# v1_3SMD.net
KiCad netlist of a schematic drawn in EAGLE
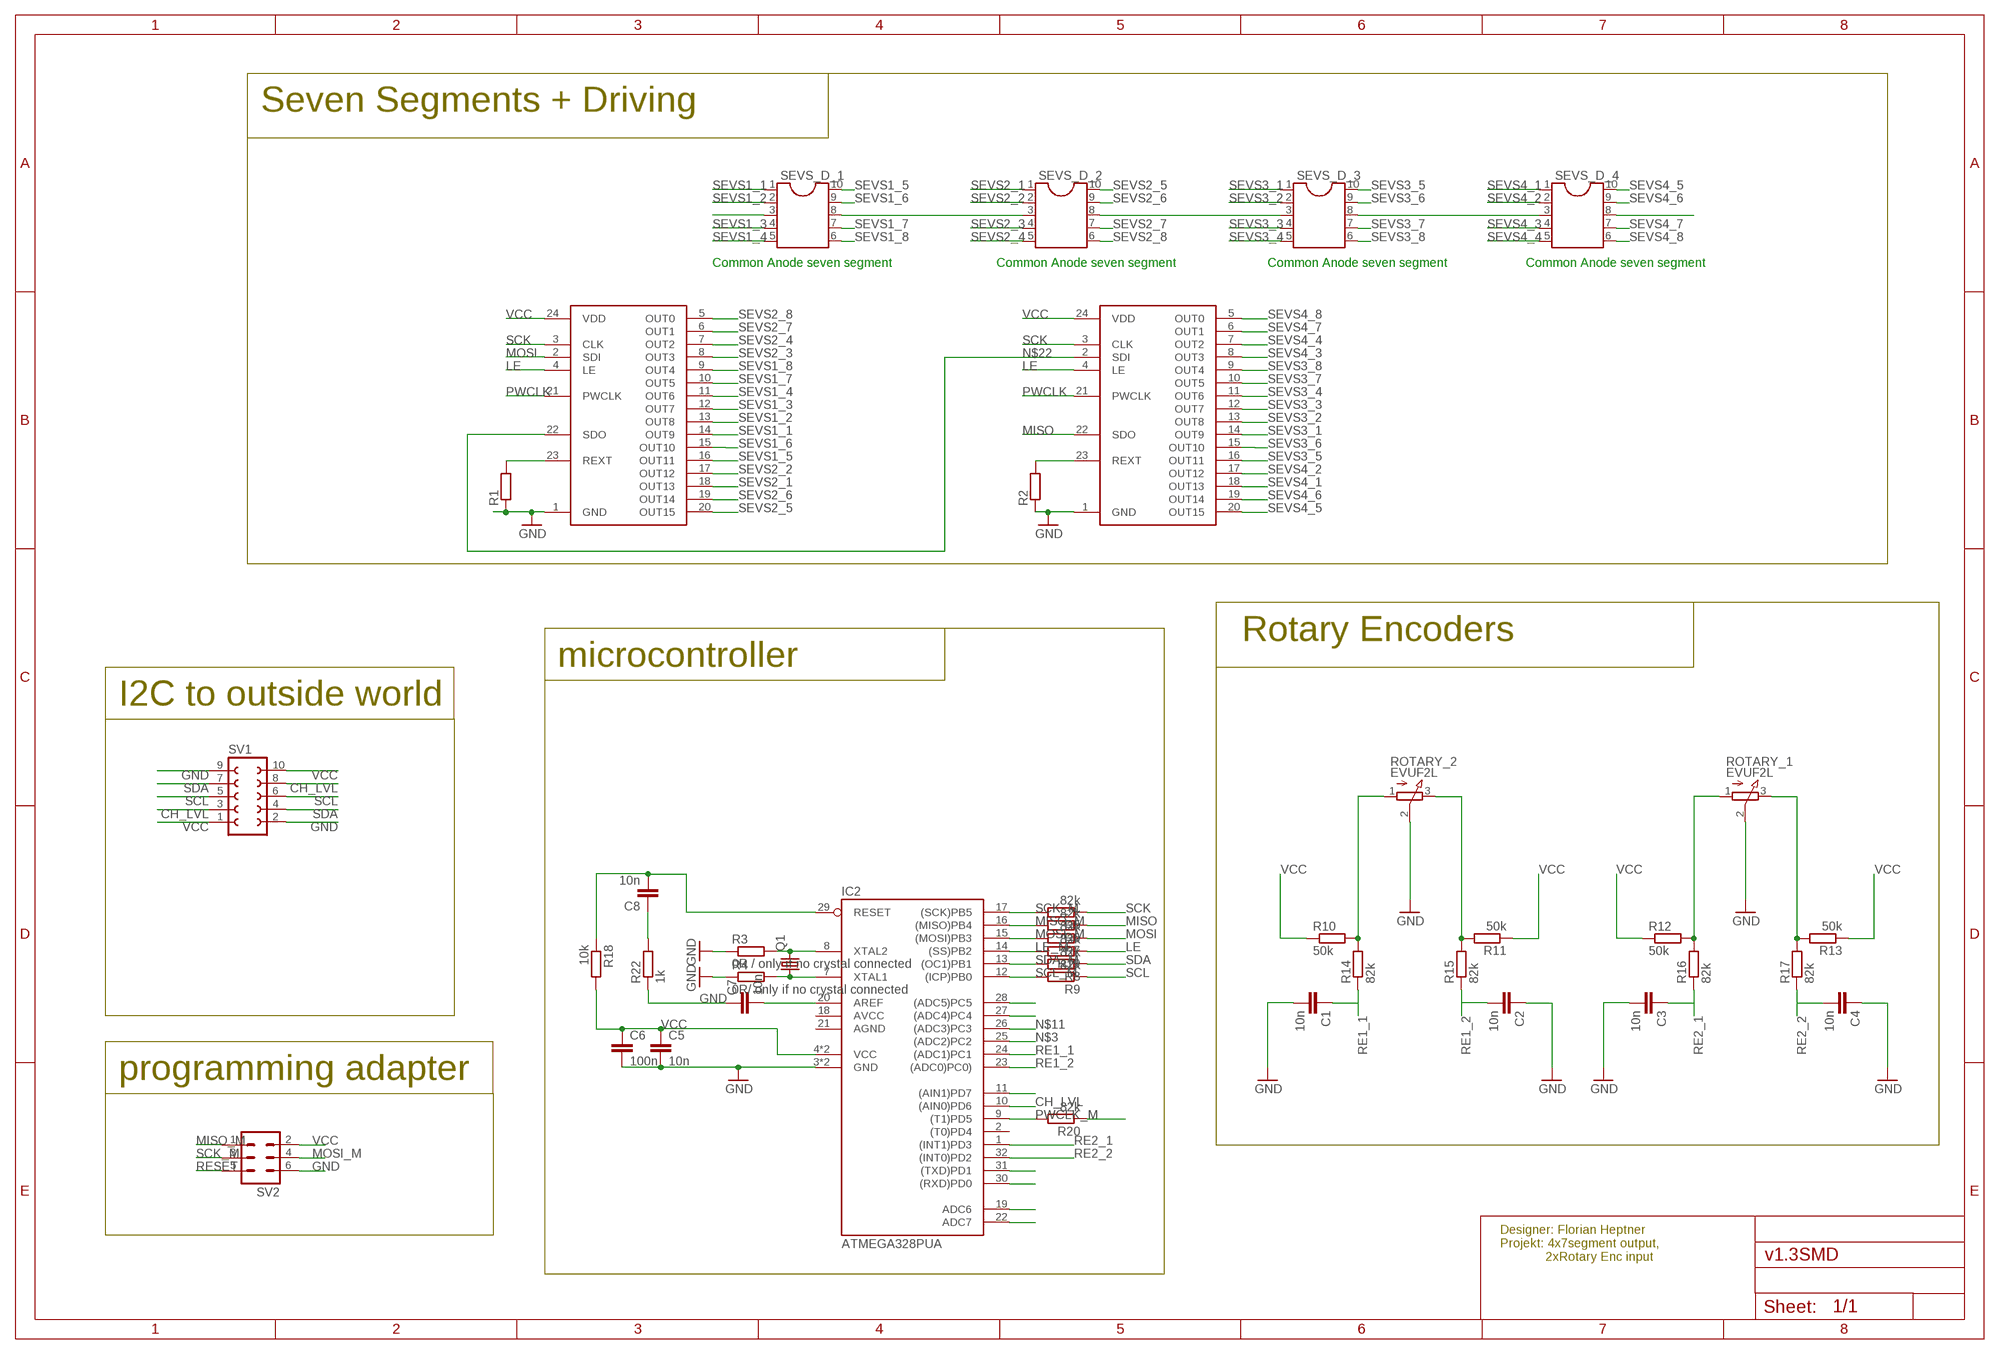
[diagram p0: schematic, sheet 1]

(export (version "E")
  (design (tool "Eeschema 10.0.6"))
  (components
    (comp (ref "C1")
      (value "10n")
      (footprint "eagle-import:C0603")
      (libsource (lib "eagle-import") (part "C-EUC0603"))
    )
    (comp (ref "C2")
      (value "10n")
      (footprint "eagle-import:C0603")
      (libsource (lib "eagle-import") (part "C-EUC0603"))
    )
    (comp (ref "C3")
      (value "10n")
      (footprint "eagle-import:C0603")
      (libsource (lib "eagle-import") (part "C-EUC0603"))
    )
    (comp (ref "C4")
      (value "10n")
      (footprint "eagle-import:C0603")
      (libsource (lib "eagle-import") (part "C-EUC0603"))
    )
    (comp (ref "C5")
      (value "10n")
      (footprint "eagle-import:C0603")
      (libsource (lib "eagle-import") (part "C-EUC0603"))
    )
    (comp (ref "C6")
      (value "100n")
      (footprint "eagle-import:C0603")
      (libsource (lib "eagle-import") (part "C-EUC0603"))
    )
    (comp (ref "C7")
      (value "10n")
      (footprint "eagle-import:C0603")
      (libsource (lib "eagle-import") (part "C-EUC0603"))
    )
    (comp (ref "C8")
      (value "10n")
      (footprint "eagle-import:C0603")
      (libsource (lib "eagle-import") (part "C-EUC0603"))
    )
    (comp (ref "IC2")
      (value "ATMEGA328PUA")
      (footprint "eagle-import:TQFP32-08")
      (libsource (lib "eagle-import") (part "ATMEGA328PUA"))
    )
    (comp (ref "Q1")
      (value "CRYSTALSM49")
      (footprint "eagle-import:SM49")
      (libsource (lib "eagle-import") (part "CRYSTALSM49"))
    )
    (comp (ref "R1")
      (value "R-EU_R0603")
      (footprint "eagle-import:R0603")
      (libsource (lib "eagle-import") (part "R-EU_R0603"))
    )
    (comp (ref "R2")
      (value "R-EU_R0603")
      (footprint "eagle-import:R0603")
      (libsource (lib "eagle-import") (part "R-EU_R0603"))
    )
    (comp (ref "R3")
      (value "0R / only if no crystal connected")
      (footprint "eagle-import:R0603")
      (libsource (lib "eagle-import") (part "R-EU_R0603"))
    )
    (comp (ref "R4")
      (value "0R/ only if no crystal connected")
      (footprint "eagle-import:R0603")
      (libsource (lib "eagle-import") (part "R-EU_R0603"))
    )
    (comp (ref "R5")
      (value "82k")
      (footprint "eagle-import:R0603")
      (libsource (lib "eagle-import") (part "R-EU_R0603"))
    )
    (comp (ref "R6")
      (value "82k")
      (footprint "eagle-import:R0603")
      (libsource (lib "eagle-import") (part "R-EU_R0603"))
    )
    (comp (ref "R7")
      (value "82k")
      (footprint "eagle-import:R0603")
      (libsource (lib "eagle-import") (part "R-EU_R0603"))
    )
    (comp (ref "R8")
      (value "82k")
      (footprint "eagle-import:R0603")
      (libsource (lib "eagle-import") (part "R-EU_R0603"))
    )
    (comp (ref "R9")
      (value "82k")
      (footprint "eagle-import:R0603")
      (libsource (lib "eagle-import") (part "R-EU_R0603"))
    )
    (comp (ref "R10")
      (value "50k")
      (footprint "eagle-import:R0603")
      (libsource (lib "eagle-import") (part "R-EU_R0603"))
    )
    (comp (ref "R11")
      (value "50k")
      (footprint "eagle-import:R0603")
      (libsource (lib "eagle-import") (part "R-EU_R0603"))
    )
    (comp (ref "R12")
      (value "50k")
      (footprint "eagle-import:R0603")
      (libsource (lib "eagle-import") (part "R-EU_R0603"))
    )
    (comp (ref "R13")
      (value "50k")
      (footprint "eagle-import:R0603")
      (libsource (lib "eagle-import") (part "R-EU_R0603"))
    )
    (comp (ref "R14")
      (value "82k")
      (footprint "eagle-import:R0603")
      (libsource (lib "eagle-import") (part "R-EU_R0603"))
    )
    (comp (ref "R15")
      (value "82k")
      (footprint "eagle-import:R0603")
      (libsource (lib "eagle-import") (part "R-EU_R0603"))
    )
    (comp (ref "R16")
      (value "82k")
      (footprint "eagle-import:R0603")
      (libsource (lib "eagle-import") (part "R-EU_R0603"))
    )
    (comp (ref "R17")
      (value "82k")
      (footprint "eagle-import:R0603")
      (libsource (lib "eagle-import") (part "R-EU_R0603"))
    )
    (comp (ref "R18")
      (value "10k")
      (footprint "eagle-import:R0603")
      (libsource (lib "eagle-import") (part "R-EU_R0603"))
    )
    (comp (ref "R19")
      (value "82k")
      (footprint "eagle-import:R0603")
      (libsource (lib "eagle-import") (part "R-EU_R0603"))
    )
    (comp (ref "R20")
      (value "82k")
      (footprint "eagle-import:R0603")
      (libsource (lib "eagle-import") (part "R-EU_R0603"))
    )
    (comp (ref "R22")
      (value "1k")
      (footprint "eagle-import:R0603")
      (libsource (lib "eagle-import") (part "R-EU_R0603"))
    )
    (comp (ref "ROTARY_1")
      (value "EVUF2L")
      (footprint "eagle-import:EVUFXL")
      (libsource (lib "eagle-import") (part "EVULF2"))
    )
    (comp (ref "ROTARY_2")
      (value "EVUF2L")
      (footprint "eagle-import:EVUFXL")
      (libsource (lib "eagle-import") (part "EVULF2"))
    )
    (comp (ref "SEVS_D_1")
      (value "DIL10")
      (footprint "eagle-import:DIL10")
      (libsource (lib "eagle-import") (part "DIL10"))
    )
    (comp (ref "SEVS_D_2")
      (value "DIL10")
      (footprint "eagle-import:DIL10")
      (libsource (lib "eagle-import") (part "DIL10"))
    )
    (comp (ref "SEVS_D_3")
      (value "DIL10")
      (footprint "eagle-import:DIL10")
      (libsource (lib "eagle-import") (part "DIL10"))
    )
    (comp (ref "SEVS_D_4")
      (value "DIL10")
      (footprint "eagle-import:DIL10")
      (libsource (lib "eagle-import") (part "DIL10"))
    )
    (comp (ref "SV1")
      (value "FE05-2")
      (footprint "eagle-import:FE05-2")
      (libsource (lib "eagle-import") (part "FE05-2"))
    )
    (comp (ref "SV2")
      (value "ML6")
      (footprint "eagle-import:ML6")
      (libsource (lib "eagle-import") (part "ML6"))
    )
    (comp (ref "U$1")
      (value "SPILEDDRIVER")
      (footprint "eagle-import:TSSOP24")
      (libsource (lib "eagle-import") (part "SPILEDDRIVER"))
    )
    (comp (ref "U$2")
      (value "SPILEDDRIVER")
      (footprint "eagle-import:TSSOP24")
      (libsource (lib "eagle-import") (part "SPILEDDRIVER"))
    )
  )
  (nets
    (net (code "1") (name "/AGND") (class "Default")
      (node (ref "IC2") (pin "21") (pinfunction "AGND_21") (pintype "power_in"))
    )
    (net (code "2") (name "/AVCC") (class "Default")
      (node (ref "IC2") (pin "18") (pinfunction "AVCC_18") (pintype "power_in"))
    )
    (net (code "3") (name "/CH_LVL") (class "Default")
      (node (ref "IC2") (pin "10") (pinfunction "(AIN0)PD6_10") (pintype "bidirectional"))
      (node (ref "SV1") (pin "3") (pinfunction "3_3") (pintype "passive"))
      (node (ref "SV1") (pin "8") (pinfunction "8_8") (pintype "passive"))
    )
    (net (code "4") (name "/LE") (class "Default")
      (node (ref "R19") (pin "1") (pinfunction "1_1") (pintype "passive"))
      (node (ref "U$1") (pin "4") (pinfunction "LE_4") (pintype "bidirectional"))
      (node (ref "U$2") (pin "4") (pinfunction "LE_4") (pintype "bidirectional"))
    )
    (net (code "5") (name "/LE_M") (class "Default")
      (node (ref "IC2") (pin "14") (pinfunction "(SS)PB2_14") (pintype "bidirectional"))
      (node (ref "R19") (pin "2") (pinfunction "2_2") (pintype "passive"))
    )
    (net (code "6") (name "/MISO") (class "Default")
      (node (ref "R6") (pin "1") (pinfunction "1_1") (pintype "passive"))
      (node (ref "U$2") (pin "22") (pinfunction "SDO_22") (pintype "bidirectional"))
    )
    (net (code "7") (name "/MISO_M") (class "Default")
      (node (ref "IC2") (pin "16") (pinfunction "(MISO)PB4_16") (pintype "bidirectional"))
      (node (ref "R6") (pin "2") (pinfunction "2_2") (pintype "passive"))
      (node (ref "SV2") (pin "1") (pinfunction "1_1") (pintype "passive"))
    )
    (net (code "8") (name "/MOSI") (class "Default")
      (node (ref "R7") (pin "1") (pinfunction "1_1") (pintype "passive"))
      (node (ref "U$1") (pin "2") (pinfunction "SDI_2") (pintype "bidirectional"))
    )
    (net (code "9") (name "/MOSI_M") (class "Default")
      (node (ref "IC2") (pin "15") (pinfunction "(MOSI)PB3_15") (pintype "bidirectional"))
      (node (ref "R7") (pin "2") (pinfunction "2_2") (pintype "passive"))
      (node (ref "SV2") (pin "4") (pinfunction "4_4") (pintype "passive"))
    )
    (net (code "10") (name "/N$3") (class "Default")
      (node (ref "IC2") (pin "25") (pinfunction "(ADC2)PC2_25") (pintype "bidirectional"))
    )
    (net (code "11") (name "/N$11") (class "Default")
      (node (ref "IC2") (pin "26") (pinfunction "(ADC3)PC3_26") (pintype "bidirectional"))
    )
    (net (code "12") (name "/N$22") (class "Default")
      (node (ref "U$1") (pin "22") (pinfunction "SDO_22") (pintype "bidirectional"))
      (node (ref "U$2") (pin "2") (pinfunction "SDI_2") (pintype "bidirectional"))
    )
    (net (code "13") (name "/PWCLK") (class "Default")
      (node (ref "R20") (pin "1") (pinfunction "1_1") (pintype "passive"))
      (node (ref "U$1") (pin "21") (pinfunction "PWCLK_21") (pintype "bidirectional"))
      (node (ref "U$2") (pin "21") (pinfunction "PWCLK_21") (pintype "bidirectional"))
    )
    (net (code "14") (name "/PWCLK_M") (class "Default")
      (node (ref "IC2") (pin "9") (pinfunction "(T1)PD5_9") (pintype "bidirectional"))
      (node (ref "R20") (pin "2") (pinfunction "2_2") (pintype "passive"))
    )
    (net (code "15") (name "/RE1_1") (class "Default")
      (node (ref "C1") (pin "1") (pinfunction "1_1") (pintype "passive"))
      (node (ref "IC2") (pin "24") (pinfunction "(ADC1)PC1_24") (pintype "bidirectional"))
      (node (ref "R14") (pin "1") (pinfunction "1_1") (pintype "passive"))
    )
    (net (code "16") (name "/RE1_2") (class "Default")
      (node (ref "C2") (pin "2") (pinfunction "2_2") (pintype "passive"))
      (node (ref "IC2") (pin "23") (pinfunction "(ADC0)PC0)_23") (pintype "bidirectional"))
      (node (ref "R15") (pin "1") (pinfunction "1_1") (pintype "passive"))
    )
    (net (code "17") (name "/RE2_1") (class "Default")
      (node (ref "C3") (pin "1") (pinfunction "1_1") (pintype "passive"))
      (node (ref "IC2") (pin "1") (pinfunction "(INT1)PD3_1") (pintype "bidirectional"))
      (node (ref "R16") (pin "1") (pinfunction "1_1") (pintype "passive"))
    )
    (net (code "18") (name "/RE2_2") (class "Default")
      (node (ref "C4") (pin "2") (pinfunction "2_2") (pintype "passive"))
      (node (ref "IC2") (pin "32") (pinfunction "(INT0)PD2_32") (pintype "bidirectional"))
      (node (ref "R17") (pin "1") (pinfunction "1_1") (pintype "passive"))
    )
    (net (code "19") (name "/RESET") (class "Default")
      (node (ref "C8") (pin "2") (pinfunction "2_2") (pintype "passive"))
      (node (ref "IC2") (pin "29") (pinfunction "RESET_29") (pintype "input"))
      (node (ref "R18") (pin "1") (pinfunction "1_1") (pintype "passive"))
      (node (ref "SV2") (pin "5") (pinfunction "5_5") (pintype "passive"))
    )
    (net (code "20") (name "/SCK") (class "Default")
      (node (ref "R5") (pin "1") (pinfunction "1_1") (pintype "passive"))
      (node (ref "U$1") (pin "3") (pinfunction "CLK_3") (pintype "bidirectional"))
      (node (ref "U$2") (pin "3") (pinfunction "CLK_3") (pintype "bidirectional"))
    )
    (net (code "21") (name "/SCK_M") (class "Default")
      (node (ref "IC2") (pin "17") (pinfunction "(SCK)PB5_17") (pintype "bidirectional"))
      (node (ref "R5") (pin "2") (pinfunction "2_2") (pintype "passive"))
      (node (ref "SV2") (pin "3") (pinfunction "3_3") (pintype "passive"))
    )
    (net (code "22") (name "/SCL") (class "Default")
      (node (ref "R9") (pin "1") (pinfunction "1_1") (pintype "passive"))
      (node (ref "SV1") (pin "5") (pinfunction "5_5") (pintype "passive"))
      (node (ref "SV1") (pin "6") (pinfunction "6_6") (pintype "passive"))
    )
    (net (code "23") (name "/SCL_M") (class "Default")
      (node (ref "IC2") (pin "12") (pinfunction "(ICP)PB0_12") (pintype "bidirectional"))
      (node (ref "R9") (pin "2") (pinfunction "2_2") (pintype "passive"))
    )
    (net (code "24") (name "/SDA") (class "Default")
      (node (ref "R8") (pin "1") (pinfunction "1_1") (pintype "passive"))
      (node (ref "SV1") (pin "4") (pinfunction "4_4") (pintype "passive"))
      (node (ref "SV1") (pin "7") (pinfunction "7_7") (pintype "passive"))
    )
    (net (code "25") (name "/SDA_M") (class "Default")
      (node (ref "IC2") (pin "13") (pinfunction "(OC1)PB1_13") (pintype "bidirectional"))
      (node (ref "R8") (pin "2") (pinfunction "2_2") (pintype "passive"))
    )
    (net (code "26") (name "/SEVS1_1") (class "Default")
      (node (ref "SEVS_D_1") (pin "1") (pinfunction "1_1") (pintype "passive"))
      (node (ref "U$1") (pin "14") (pinfunction "OUT9_14") (pintype "bidirectional"))
    )
    (net (code "27") (name "/SEVS1_2") (class "Default")
      (node (ref "SEVS_D_1") (pin "2") (pinfunction "2_2") (pintype "passive"))
      (node (ref "U$1") (pin "13") (pinfunction "OUT8_13") (pintype "bidirectional"))
    )
    (net (code "28") (name "/SEVS1_3") (class "Default")
      (node (ref "SEVS_D_1") (pin "4") (pinfunction "4_4") (pintype "passive"))
      (node (ref "U$1") (pin "12") (pinfunction "OUT7_12") (pintype "bidirectional"))
    )
    (net (code "29") (name "/SEVS1_4") (class "Default")
      (node (ref "SEVS_D_1") (pin "5") (pinfunction "5_5") (pintype "passive"))
      (node (ref "U$1") (pin "11") (pinfunction "OUT6_11") (pintype "bidirectional"))
    )
    (net (code "30") (name "/SEVS1_5") (class "Default")
      (node (ref "SEVS_D_1") (pin "10") (pinfunction "10_10") (pintype "passive"))
      (node (ref "U$1") (pin "16") (pinfunction "OUT11_16") (pintype "bidirectional"))
    )
    (net (code "31") (name "/SEVS1_6") (class "Default")
      (node (ref "SEVS_D_1") (pin "9") (pinfunction "9_9") (pintype "passive"))
      (node (ref "U$1") (pin "15") (pinfunction "OUT10_15") (pintype "bidirectional"))
    )
    (net (code "32") (name "/SEVS1_7") (class "Default")
      (node (ref "SEVS_D_1") (pin "7") (pinfunction "7_7") (pintype "passive"))
      (node (ref "U$1") (pin "10") (pinfunction "OUT5_10") (pintype "bidirectional"))
    )
    (net (code "33") (name "/SEVS1_8") (class "Default")
      (node (ref "SEVS_D_1") (pin "6") (pinfunction "6_6") (pintype "passive"))
      (node (ref "U$1") (pin "9") (pinfunction "OUT4_9") (pintype "bidirectional"))
    )
    (net (code "34") (name "/SEVS2_1") (class "Default")
      (node (ref "SEVS_D_2") (pin "1") (pinfunction "1_1") (pintype "passive"))
      (node (ref "U$1") (pin "18") (pinfunction "OUT13_18") (pintype "bidirectional"))
    )
    (net (code "35") (name "/SEVS2_2") (class "Default")
      (node (ref "SEVS_D_2") (pin "2") (pinfunction "2_2") (pintype "passive"))
      (node (ref "U$1") (pin "17") (pinfunction "OUT12_17") (pintype "bidirectional"))
    )
    (net (code "36") (name "/SEVS2_3") (class "Default")
      (node (ref "SEVS_D_2") (pin "4") (pinfunction "4_4") (pintype "passive"))
      (node (ref "U$1") (pin "8") (pinfunction "OUT3_8") (pintype "bidirectional"))
    )
    (net (code "37") (name "/SEVS2_4") (class "Default")
      (node (ref "SEVS_D_2") (pin "5") (pinfunction "5_5") (pintype "passive"))
      (node (ref "U$1") (pin "7") (pinfunction "OUT2_7") (pintype "bidirectional"))
    )
    (net (code "38") (name "/SEVS2_5") (class "Default")
      (node (ref "SEVS_D_2") (pin "10") (pinfunction "10_10") (pintype "passive"))
      (node (ref "U$1") (pin "20") (pinfunction "OUT15_20") (pintype "bidirectional"))
    )
    (net (code "39") (name "/SEVS2_6") (class "Default")
      (node (ref "SEVS_D_2") (pin "9") (pinfunction "9_9") (pintype "passive"))
      (node (ref "U$1") (pin "19") (pinfunction "OUT14_19") (pintype "bidirectional"))
    )
    (net (code "40") (name "/SEVS2_7") (class "Default")
      (node (ref "SEVS_D_2") (pin "7") (pinfunction "7_7") (pintype "passive"))
      (node (ref "U$1") (pin "6") (pinfunction "OUT1_6") (pintype "bidirectional"))
    )
    (net (code "41") (name "/SEVS2_8") (class "Default")
      (node (ref "SEVS_D_2") (pin "6") (pinfunction "6_6") (pintype "passive"))
      (node (ref "U$1") (pin "5") (pinfunction "OUT0_5") (pintype "bidirectional"))
    )
    (net (code "42") (name "/SEVS3_1") (class "Default")
      (node (ref "SEVS_D_3") (pin "1") (pinfunction "1_1") (pintype "passive"))
      (node (ref "U$2") (pin "14") (pinfunction "OUT9_14") (pintype "bidirectional"))
    )
    (net (code "43") (name "/SEVS3_2") (class "Default")
      (node (ref "SEVS_D_3") (pin "2") (pinfunction "2_2") (pintype "passive"))
      (node (ref "U$2") (pin "13") (pinfunction "OUT8_13") (pintype "bidirectional"))
    )
    (net (code "44") (name "/SEVS3_3") (class "Default")
      (node (ref "SEVS_D_3") (pin "4") (pinfunction "4_4") (pintype "passive"))
      (node (ref "U$2") (pin "12") (pinfunction "OUT7_12") (pintype "bidirectional"))
    )
    (net (code "45") (name "/SEVS3_4") (class "Default")
      (node (ref "SEVS_D_3") (pin "5") (pinfunction "5_5") (pintype "passive"))
      (node (ref "U$2") (pin "11") (pinfunction "OUT6_11") (pintype "bidirectional"))
    )
    (net (code "46") (name "/SEVS3_5") (class "Default")
      (node (ref "SEVS_D_3") (pin "10") (pinfunction "10_10") (pintype "passive"))
      (node (ref "U$2") (pin "16") (pinfunction "OUT11_16") (pintype "bidirectional"))
    )
    (net (code "47") (name "/SEVS3_6") (class "Default")
      (node (ref "SEVS_D_3") (pin "9") (pinfunction "9_9") (pintype "passive"))
      (node (ref "U$2") (pin "15") (pinfunction "OUT10_15") (pintype "bidirectional"))
    )
    (net (code "48") (name "/SEVS3_7") (class "Default")
      (node (ref "SEVS_D_3") (pin "7") (pinfunction "7_7") (pintype "passive"))
      (node (ref "U$2") (pin "10") (pinfunction "OUT5_10") (pintype "bidirectional"))
    )
    (net (code "49") (name "/SEVS3_8") (class "Default")
      (node (ref "SEVS_D_3") (pin "6") (pinfunction "6_6") (pintype "passive"))
      (node (ref "U$2") (pin "9") (pinfunction "OUT4_9") (pintype "bidirectional"))
    )
    (net (code "50") (name "/SEVS4_1") (class "Default")
      (node (ref "SEVS_D_4") (pin "1") (pinfunction "1_1") (pintype "passive"))
      (node (ref "U$2") (pin "18") (pinfunction "OUT13_18") (pintype "bidirectional"))
    )
    (net (code "51") (name "/SEVS4_2") (class "Default")
      (node (ref "SEVS_D_4") (pin "2") (pinfunction "2_2") (pintype "passive"))
      (node (ref "U$2") (pin "17") (pinfunction "OUT12_17") (pintype "bidirectional"))
    )
    (net (code "52") (name "/SEVS4_3") (class "Default")
      (node (ref "SEVS_D_4") (pin "4") (pinfunction "4_4") (pintype "passive"))
      (node (ref "U$2") (pin "8") (pinfunction "OUT3_8") (pintype "bidirectional"))
    )
    (net (code "53") (name "/SEVS4_4") (class "Default")
      (node (ref "SEVS_D_4") (pin "5") (pinfunction "5_5") (pintype "passive"))
      (node (ref "U$2") (pin "7") (pinfunction "OUT2_7") (pintype "bidirectional"))
    )
    (net (code "54") (name "/SEVS4_5") (class "Default")
      (node (ref "SEVS_D_4") (pin "10") (pinfunction "10_10") (pintype "passive"))
      (node (ref "U$2") (pin "20") (pinfunction "OUT15_20") (pintype "bidirectional"))
    )
    (net (code "55") (name "/SEVS4_6") (class "Default")
      (node (ref "SEVS_D_4") (pin "9") (pinfunction "9_9") (pintype "passive"))
      (node (ref "U$2") (pin "19") (pinfunction "OUT14_19") (pintype "bidirectional"))
    )
    (net (code "56") (name "/SEVS4_7") (class "Default")
      (node (ref "SEVS_D_4") (pin "7") (pinfunction "7_7") (pintype "passive"))
      (node (ref "U$2") (pin "6") (pinfunction "OUT1_6") (pintype "bidirectional"))
    )
    (net (code "57") (name "/SEVS4_8") (class "Default")
      (node (ref "SEVS_D_4") (pin "6") (pinfunction "6_6") (pintype "passive"))
      (node (ref "U$2") (pin "5") (pinfunction "OUT0_5") (pintype "bidirectional"))
    )
    (net (code "58") (name "/VCC") (class "Default")
      (node (ref "C5") (pin "1") (pinfunction "1_1") (pintype "passive"))
      (node (ref "C6") (pin "1") (pinfunction "1_1") (pintype "passive"))
      (node (ref "IC2") (pin "4") (pinfunction "VCC_4") (pintype "power_in"))
      (node (ref "IC2") (pin "6") (pinfunction "VCC_6") (pintype "power_in"))
      (node (ref "R10") (pin "1") (pinfunction "1_1") (pintype "passive"))
      (node (ref "R11") (pin "1") (pinfunction "1_1") (pintype "passive"))
      (node (ref "R12") (pin "1") (pinfunction "1_1") (pintype "passive"))
      (node (ref "R13") (pin "1") (pinfunction "1_1") (pintype "passive"))
      (node (ref "R18") (pin "2") (pinfunction "2_2") (pintype "passive"))
      (node (ref "SEVS_D_1") (pin "3") (pinfunction "3_3") (pintype "passive"))
      (node (ref "SEVS_D_1") (pin "8") (pinfunction "8_8") (pintype "passive"))
      (node (ref "SEVS_D_2") (pin "3") (pinfunction "3_3") (pintype "passive"))
      (node (ref "SEVS_D_2") (pin "8") (pinfunction "8_8") (pintype "passive"))
      (node (ref "SEVS_D_3") (pin "3") (pinfunction "3_3") (pintype "passive"))
      (node (ref "SEVS_D_3") (pin "8") (pinfunction "8_8") (pintype "passive"))
      (node (ref "SEVS_D_4") (pin "3") (pinfunction "3_3") (pintype "passive"))
      (node (ref "SEVS_D_4") (pin "8") (pinfunction "8_8") (pintype "passive"))
      (node (ref "SV1") (pin "1") (pinfunction "1_1") (pintype "passive"))
      (node (ref "SV1") (pin "10") (pinfunction "10_10") (pintype "passive"))
      (node (ref "SV2") (pin "2") (pinfunction "2_2") (pintype "passive"))
      (node (ref "U$1") (pin "24") (pinfunction "VDD_24") (pintype "bidirectional"))
      (node (ref "U$2") (pin "24") (pinfunction "VDD_24") (pintype "bidirectional"))
    )
    (net (code "59") (name "GND") (class "Default")
      (node (ref "C1") (pin "2") (pinfunction "2_2") (pintype "passive"))
      (node (ref "C2") (pin "1") (pinfunction "1_1") (pintype "passive"))
      (node (ref "C3") (pin "2") (pinfunction "2_2") (pintype "passive"))
      (node (ref "C4") (pin "1") (pinfunction "1_1") (pintype "passive"))
      (node (ref "C5") (pin "2") (pinfunction "2_2") (pintype "passive"))
      (node (ref "C6") (pin "2") (pinfunction "2_2") (pintype "passive"))
      (node (ref "C7") (pin "1") (pinfunction "1_1") (pintype "passive"))
      (node (ref "IC2") (pin "3") (pinfunction "GND_3") (pintype "power_in"))
      (node (ref "IC2") (pin "5") (pinfunction "GND_5") (pintype "power_in"))
      (node (ref "R1") (pin "1") (pinfunction "1_1") (pintype "passive"))
      (node (ref "R2") (pin "1") (pinfunction "1_1") (pintype "passive"))
      (node (ref "R22") (pin "1") (pinfunction "1_1") (pintype "passive"))
      (node (ref "R3") (pin "1") (pinfunction "1_1") (pintype "passive"))
      (node (ref "R4") (pin "1") (pinfunction "1_1") (pintype "passive"))
      (node (ref "ROTARY_1") (pin "2") (pinfunction "S_2") (pintype "passive"))
      (node (ref "ROTARY_2") (pin "2") (pinfunction "S_2") (pintype "passive"))
      (node (ref "SV1") (pin "2") (pinfunction "2_2") (pintype "passive"))
      (node (ref "SV1") (pin "9") (pinfunction "9_9") (pintype "passive"))
      (node (ref "SV2") (pin "6") (pinfunction "6_6") (pintype "passive"))
      (node (ref "U$1") (pin "1") (pinfunction "GND_1") (pintype "bidirectional"))
      (node (ref "U$2") (pin "1") (pinfunction "GND_1") (pintype "bidirectional"))
    )
    (net (code "60") (name "Net-(C8-Pad1)") (class "Default")
      (node (ref "C8") (pin "1") (pinfunction "1_1") (pintype "passive"))
      (node (ref "R22") (pin "2") (pinfunction "2_2") (pintype "passive"))
    )
    (net (code "61") (name "Net-(IC2-AREF)") (class "Default")
      (node (ref "C7") (pin "2") (pinfunction "2_2") (pintype "passive"))
      (node (ref "IC2") (pin "20") (pinfunction "AREF_20") (pintype "passive"))
    )
    (net (code "62") (name "Net-(IC2-XTAL1)") (class "Default")
      (node (ref "IC2") (pin "7") (pinfunction "XTAL1_7") (pintype "bidirectional"))
      (node (ref "Q1") (pin "1") (pinfunction "1_1") (pintype "passive"))
      (node (ref "R4") (pin "2") (pinfunction "2_2") (pintype "passive"))
    )
    (net (code "63") (name "Net-(IC2-XTAL2)") (class "Default")
      (node (ref "IC2") (pin "8") (pinfunction "XTAL2_8") (pintype "bidirectional"))
      (node (ref "Q1") (pin "2") (pinfunction "2_2") (pintype "passive"))
      (node (ref "R3") (pin "2") (pinfunction "2_2") (pintype "passive"))
    )
    (net (code "64") (name "Net-(ROTARY_1-A)") (class "Default")
      (node (ref "R12") (pin "2") (pinfunction "2_2") (pintype "passive"))
      (node (ref "R16") (pin "2") (pinfunction "2_2") (pintype "passive"))
      (node (ref "ROTARY_1") (pin "1") (pinfunction "A_1") (pintype "passive"))
    )
    (net (code "65") (name "Net-(ROTARY_1-E)") (class "Default")
      (node (ref "R13") (pin "2") (pinfunction "2_2") (pintype "passive"))
      (node (ref "R17") (pin "2") (pinfunction "2_2") (pintype "passive"))
      (node (ref "ROTARY_1") (pin "3") (pinfunction "E_3") (pintype "passive"))
    )
    (net (code "66") (name "Net-(ROTARY_2-A)") (class "Default")
      (node (ref "R10") (pin "2") (pinfunction "2_2") (pintype "passive"))
      (node (ref "R14") (pin "2") (pinfunction "2_2") (pintype "passive"))
      (node (ref "ROTARY_2") (pin "1") (pinfunction "A_1") (pintype "passive"))
    )
    (net (code "67") (name "Net-(ROTARY_2-E)") (class "Default")
      (node (ref "R11") (pin "2") (pinfunction "2_2") (pintype "passive"))
      (node (ref "R15") (pin "2") (pinfunction "2_2") (pintype "passive"))
      (node (ref "ROTARY_2") (pin "3") (pinfunction "E_3") (pintype "passive"))
    )
    (net (code "68") (name "Net-(U$1-REXT)") (class "Default")
      (node (ref "R1") (pin "2") (pinfunction "2_2") (pintype "passive"))
      (node (ref "U$1") (pin "23") (pinfunction "REXT_23") (pintype "bidirectional"))
    )
    (net (code "69") (name "Net-(U$2-REXT)") (class "Default")
      (node (ref "R2") (pin "2") (pinfunction "2_2") (pintype "passive"))
      (node (ref "U$2") (pin "23") (pinfunction "REXT_23") (pintype "bidirectional"))
    )
    (net (code "70") (name "unconnected-(IC2-(ADC4)PC4-Pad27)") (class "Default")
      (node (ref "IC2") (pin "27") (pinfunction "(ADC4)PC4_27") (pintype "bidirectional"))
    )
    (net (code "71") (name "unconnected-(IC2-(ADC5)PC5-Pad28)") (class "Default")
      (node (ref "IC2") (pin "28") (pinfunction "(ADC5)PC5_28") (pintype "bidirectional"))
    )
    (net (code "72") (name "unconnected-(IC2-(AIN1)PD7-Pad11)") (class "Default")
      (node (ref "IC2") (pin "11") (pinfunction "(AIN1)PD7_11") (pintype "bidirectional"))
    )
    (net (code "73") (name "unconnected-(IC2-(RXD)PD0-Pad30)") (class "Default")
      (node (ref "IC2") (pin "30") (pinfunction "(RXD)PD0_30") (pintype "bidirectional"))
    )
    (net (code "74") (name "unconnected-(IC2-(T0)PD4-Pad2)") (class "Default")
      (node (ref "IC2") (pin "2") (pinfunction "(T0)PD4_2") (pintype "bidirectional"))
    )
    (net (code "75") (name "unconnected-(IC2-(TXD)PD1-Pad31)") (class "Default")
      (node (ref "IC2") (pin "31") (pinfunction "(TXD)PD1_31") (pintype "bidirectional"))
    )
    (net (code "76") (name "unconnected-(IC2-ADC6-Pad19)") (class "Default")
      (node (ref "IC2") (pin "19") (pinfunction "ADC6_19") (pintype "bidirectional"))
    )
    (net (code "77") (name "unconnected-(IC2-ADC7-Pad22)") (class "Default")
      (node (ref "IC2") (pin "22") (pinfunction "ADC7_22") (pintype "bidirectional"))
    )
  )
)
